# BLDC_conmutation_module.net
KiCad netlist of a schematic drawn in EAGLE
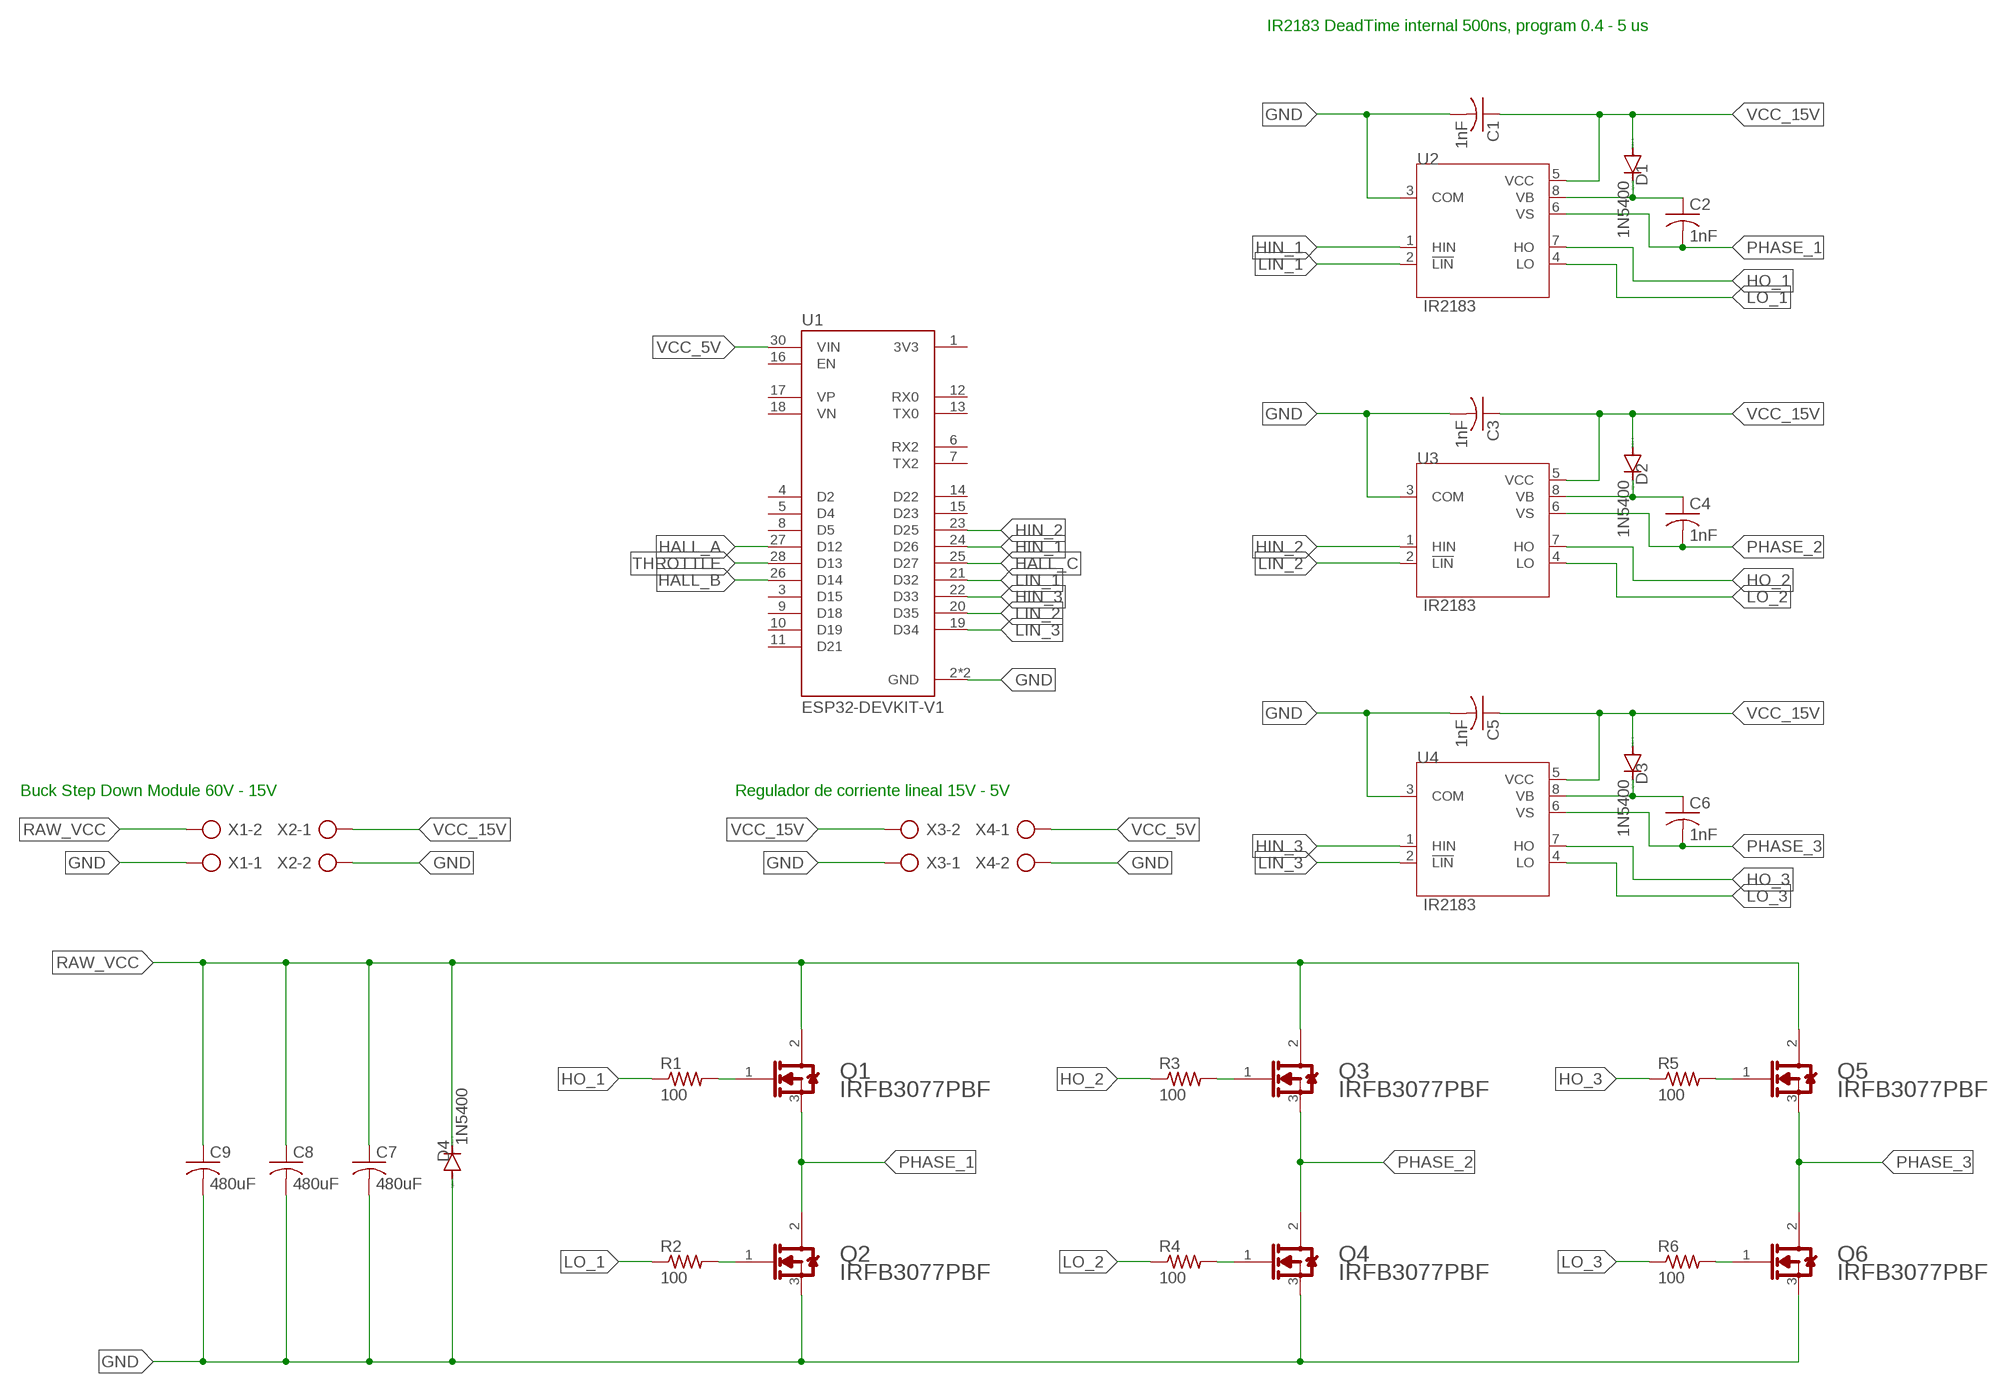
[diagram p0: schematic, sheet 1]

(export (version "E")
  (design (tool "Eeschema 10.0.6"))
  (components
    (comp (ref "C1")
      (value "1nF")
      (footprint "eagle-import:C025-050X050")
      (libsource (lib "eagle-import") (part "C-US025-050X050"))
    )
    (comp (ref "C2")
      (value "1nF")
      (footprint "eagle-import:C025-050X050")
      (libsource (lib "eagle-import") (part "C-US025-050X050"))
    )
    (comp (ref "C3")
      (value "1nF")
      (footprint "eagle-import:C025-050X050")
      (libsource (lib "eagle-import") (part "C-US025-050X050"))
    )
    (comp (ref "C4")
      (value "1nF")
      (footprint "eagle-import:C025-050X050")
      (libsource (lib "eagle-import") (part "C-US025-050X050"))
    )
    (comp (ref "C5")
      (value "1nF")
      (footprint "eagle-import:C025-050X050")
      (libsource (lib "eagle-import") (part "C-US025-050X050"))
    )
    (comp (ref "C6")
      (value "1nF")
      (footprint "eagle-import:C025-050X050")
      (libsource (lib "eagle-import") (part "C-US025-050X050"))
    )
    (comp (ref "C7")
      (value "480uF")
      (footprint "eagle-import:C025-050X050")
      (libsource (lib "eagle-import") (part "C-US025-050X050"))
    )
    (comp (ref "C8")
      (value "480uF")
      (footprint "eagle-import:C025-050X050")
      (libsource (lib "eagle-import") (part "C-US025-050X050"))
    )
    (comp (ref "C9")
      (value "480uF")
      (footprint "eagle-import:C025-050X050")
      (libsource (lib "eagle-import") (part "C-US025-050X050"))
    )
    (comp (ref "D1")
      (value "1N5400")
      (footprint "eagle-import:DO201-15")
      (libsource (lib "eagle-import") (part "1N5400"))
    )
    (comp (ref "D2")
      (value "1N5400")
      (footprint "eagle-import:DO201-15")
      (libsource (lib "eagle-import") (part "1N5400"))
    )
    (comp (ref "D3")
      (value "1N5400")
      (footprint "eagle-import:DO201-15")
      (libsource (lib "eagle-import") (part "1N5400"))
    )
    (comp (ref "D4")
      (value "1N5400")
      (footprint "eagle-import:DO201-15")
      (libsource (lib "eagle-import") (part "1N5400"))
    )
    (comp (ref "Q1")
      (value "INFINEON_IRFB3077PBFINFINEON_IRFB3077PBF_0_0")
      (footprint "eagle-import:INFINEON_IRFB3077PBF_0")
      (fields
        (field (name "DIGIKEY_PART_NUMBER") "IRFB3077PBF-ND")
        (field (name "MF") "Infineon")
        (field (name "MOUSER_PART_NUMBER") "942-IRFB3077PBF")
      )
      (libsource (lib "eagle-import") (part "INFINEON_IRFB3077PBFINFINEON_IRFB3077PBF_0_0"))
    )
    (comp (ref "Q2")
      (value "INFINEON_IRFB3077PBFINFINEON_IRFB3077PBF_0_0")
      (footprint "eagle-import:INFINEON_IRFB3077PBF_0")
      (fields
        (field (name "DIGIKEY_PART_NUMBER") "IRFB3077PBF-ND")
        (field (name "MF") "Infineon")
        (field (name "MOUSER_PART_NUMBER") "942-IRFB3077PBF")
      )
      (libsource (lib "eagle-import") (part "INFINEON_IRFB3077PBFINFINEON_IRFB3077PBF_0_0"))
    )
    (comp (ref "Q3")
      (value "INFINEON_IRFB3077PBFINFINEON_IRFB3077PBF_0_0")
      (footprint "eagle-import:INFINEON_IRFB3077PBF_0")
      (fields
        (field (name "DIGIKEY_PART_NUMBER") "IRFB3077PBF-ND")
        (field (name "MF") "Infineon")
        (field (name "MOUSER_PART_NUMBER") "942-IRFB3077PBF")
      )
      (libsource (lib "eagle-import") (part "INFINEON_IRFB3077PBFINFINEON_IRFB3077PBF_0_0"))
    )
    (comp (ref "Q4")
      (value "INFINEON_IRFB3077PBFINFINEON_IRFB3077PBF_0_0")
      (footprint "eagle-import:INFINEON_IRFB3077PBF_0")
      (fields
        (field (name "DIGIKEY_PART_NUMBER") "IRFB3077PBF-ND")
        (field (name "MF") "Infineon")
        (field (name "MOUSER_PART_NUMBER") "942-IRFB3077PBF")
      )
      (libsource (lib "eagle-import") (part "INFINEON_IRFB3077PBFINFINEON_IRFB3077PBF_0_0"))
    )
    (comp (ref "Q5")
      (value "INFINEON_IRFB3077PBFINFINEON_IRFB3077PBF_0_0")
      (footprint "eagle-import:INFINEON_IRFB3077PBF_0")
      (fields
        (field (name "DIGIKEY_PART_NUMBER") "IRFB3077PBF-ND")
        (field (name "MF") "Infineon")
        (field (name "MOUSER_PART_NUMBER") "942-IRFB3077PBF")
      )
      (libsource (lib "eagle-import") (part "INFINEON_IRFB3077PBFINFINEON_IRFB3077PBF_0_0"))
    )
    (comp (ref "Q6")
      (value "INFINEON_IRFB3077PBFINFINEON_IRFB3077PBF_0_0")
      (footprint "eagle-import:INFINEON_IRFB3077PBF_0")
      (fields
        (field (name "DIGIKEY_PART_NUMBER") "IRFB3077PBF-ND")
        (field (name "MF") "Infineon")
        (field (name "MOUSER_PART_NUMBER") "942-IRFB3077PBF")
      )
      (libsource (lib "eagle-import") (part "INFINEON_IRFB3077PBFINFINEON_IRFB3077PBF_0_0"))
    )
    (comp (ref "R1")
      (value "100")
      (footprint "eagle-import:0207_10")
      (libsource (lib "eagle-import") (part "R-US_0207/10"))
    )
    (comp (ref "R2")
      (value "100")
      (footprint "eagle-import:0207_10")
      (libsource (lib "eagle-import") (part "R-US_0207/10"))
    )
    (comp (ref "R3")
      (value "100")
      (footprint "eagle-import:0207_10")
      (libsource (lib "eagle-import") (part "R-US_0207/10"))
    )
    (comp (ref "R4")
      (value "100")
      (footprint "eagle-import:0207_10")
      (libsource (lib "eagle-import") (part "R-US_0207/10"))
    )
    (comp (ref "R5")
      (value "100")
      (footprint "eagle-import:0207_10")
      (libsource (lib "eagle-import") (part "R-US_0207/10"))
    )
    (comp (ref "R6")
      (value "100")
      (footprint "eagle-import:0207_10")
      (libsource (lib "eagle-import") (part "R-US_0207/10"))
    )
    (comp (ref "U1")
      (value "ESP32-DEVKIT-V1")
      (footprint "eagle-import:MODULE_ESP32_DEVKIT_V1")
      (fields (field (name "MF") "Do it"))
      (libsource (lib "eagle-import") (part "ESP32-DEVKIT-V1"))
    )
    (comp (ref "U2")
      (value "IR2183")
      (footprint "eagle-import:DIP762W45P254L1092H533Q8")
      (fields (field (name "MF") "Infineon"))
      (libsource (lib "eagle-import") (part "IR2183"))
    )
    (comp (ref "U3")
      (value "IR2183")
      (footprint "eagle-import:DIP762W45P254L1092H533Q8")
      (fields (field (name "MF") "Infineon"))
      (libsource (lib "eagle-import") (part "IR2183"))
    )
    (comp (ref "U4")
      (value "IR2183")
      (footprint "eagle-import:DIP762W45P254L1092H533Q8")
      (fields (field (name "MF") "Infineon"))
      (libsource (lib "eagle-import") (part "IR2183"))
    )
    (comp (ref "X1")
      (value "AK500/2-H")
      (footprint "eagle-import:AK500_2-H")
      (libsource (lib "eagle-import") (part "AK500/2-H"))
    )
    (comp (ref "X2")
      (value "AK500/2-H")
      (footprint "eagle-import:AK500_2-H")
      (libsource (lib "eagle-import") (part "AK500/2-H"))
    )
    (comp (ref "X3")
      (value "AK500/2-H")
      (footprint "eagle-import:AK500_2-H")
      (libsource (lib "eagle-import") (part "AK500/2-H"))
    )
    (comp (ref "X4")
      (value "AK500/2-H")
      (footprint "eagle-import:AK500_2-H")
      (libsource (lib "eagle-import") (part "AK500/2-H"))
    )
  )
  (nets
    (net (code "1") (name "GND") (class "Default")
      (node (ref "C1") (pin "2") (pinfunction "2_2") (pintype "passive"))
      (node (ref "C3") (pin "2") (pinfunction "2_2") (pintype "passive"))
      (node (ref "C5") (pin "2") (pinfunction "2_2") (pintype "passive"))
      (node (ref "C7") (pin "2") (pinfunction "2_2") (pintype "passive"))
      (node (ref "C8") (pin "2") (pinfunction "2_2") (pintype "passive"))
      (node (ref "C9") (pin "2") (pinfunction "2_2") (pintype "passive"))
      (node (ref "D4") (pin "A") (pinfunction "A_A") (pintype "passive"))
      (node (ref "Q2") (pin "3") (pinfunction "S_3") (pintype "output"))
      (node (ref "Q4") (pin "3") (pinfunction "S_3") (pintype "output"))
      (node (ref "Q6") (pin "3") (pinfunction "S_3") (pintype "output"))
      (node (ref "U1") (pin "2") (pinfunction "GND_2") (pintype "power_in"))
      (node (ref "U1") (pin "29") (pinfunction "GND_29") (pintype "power_in"))
      (node (ref "U2") (pin "3") (pinfunction "COM_3") (pintype "bidirectional"))
      (node (ref "U3") (pin "3") (pinfunction "COM_3") (pintype "bidirectional"))
      (node (ref "U4") (pin "3") (pinfunction "COM_3") (pintype "bidirectional"))
      (node (ref "X1") (pin "1") (pinfunction "KL_1") (pintype "passive"))
      (node (ref "X2") (pin "2") (pinfunction "KL_2") (pintype "passive"))
      (node (ref "X3") (pin "1") (pinfunction "KL_1") (pintype "passive"))
      (node (ref "X4") (pin "2") (pinfunction "KL_2") (pintype "passive"))
    )
    (net (code "2") (name "HALL_A") (class "Default")
      (node (ref "U1") (pin "27") (pinfunction "D12_27") (pintype "bidirectional"))
    )
    (net (code "3") (name "HALL_B") (class "Default")
      (node (ref "U1") (pin "26") (pinfunction "D14_26") (pintype "bidirectional"))
    )
    (net (code "4") (name "HALL_C") (class "Default")
      (node (ref "U1") (pin "25") (pinfunction "D27_25") (pintype "bidirectional"))
    )
    (net (code "5") (name "HIN_1") (class "Default")
      (node (ref "U1") (pin "24") (pinfunction "D26_24") (pintype "bidirectional"))
      (node (ref "U2") (pin "1") (pinfunction "HIN_1") (pintype "input"))
    )
    (net (code "6") (name "HIN_2") (class "Default")
      (node (ref "U1") (pin "23") (pinfunction "D25_23") (pintype "bidirectional"))
      (node (ref "U3") (pin "1") (pinfunction "HIN_1") (pintype "input"))
    )
    (net (code "7") (name "HIN_3") (class "Default")
      (node (ref "U1") (pin "22") (pinfunction "D33_22") (pintype "bidirectional"))
      (node (ref "U4") (pin "1") (pinfunction "HIN_1") (pintype "input"))
    )
    (net (code "8") (name "HO_1") (class "Default")
      (node (ref "R1") (pin "1") (pinfunction "1_1") (pintype "passive"))
      (node (ref "U2") (pin "7") (pinfunction "HO_7") (pintype "output"))
    )
    (net (code "9") (name "HO_2") (class "Default")
      (node (ref "R3") (pin "1") (pinfunction "1_1") (pintype "passive"))
      (node (ref "U3") (pin "7") (pinfunction "HO_7") (pintype "output"))
    )
    (net (code "10") (name "HO_3") (class "Default")
      (node (ref "R5") (pin "1") (pinfunction "1_1") (pintype "passive"))
      (node (ref "U4") (pin "7") (pinfunction "HO_7") (pintype "output"))
    )
    (net (code "11") (name "LIN_1") (class "Default")
      (node (ref "U1") (pin "21") (pinfunction "D32_21") (pintype "bidirectional"))
      (node (ref "U2") (pin "2") (pinfunction "~{LIN}_2") (pintype "input"))
    )
    (net (code "12") (name "LIN_2") (class "Default")
      (node (ref "U1") (pin "20") (pinfunction "D35_20") (pintype "bidirectional"))
      (node (ref "U3") (pin "2") (pinfunction "~{LIN}_2") (pintype "input"))
    )
    (net (code "13") (name "LIN_3") (class "Default")
      (node (ref "U1") (pin "19") (pinfunction "D34_19") (pintype "bidirectional"))
      (node (ref "U4") (pin "2") (pinfunction "~{LIN}_2") (pintype "input"))
    )
    (net (code "14") (name "LO_1") (class "Default")
      (node (ref "R2") (pin "1") (pinfunction "1_1") (pintype "passive"))
      (node (ref "U2") (pin "4") (pinfunction "LO_4") (pintype "output"))
    )
    (net (code "15") (name "LO_2") (class "Default")
      (node (ref "R4") (pin "1") (pinfunction "1_1") (pintype "passive"))
      (node (ref "U3") (pin "4") (pinfunction "LO_4") (pintype "output"))
    )
    (net (code "16") (name "LO_3") (class "Default")
      (node (ref "R6") (pin "1") (pinfunction "1_1") (pintype "passive"))
      (node (ref "U4") (pin "4") (pinfunction "LO_4") (pintype "output"))
    )
    (net (code "17") (name "Net-(Q1-G)") (class "Default")
      (node (ref "Q1") (pin "1") (pinfunction "G_1") (pintype "passive"))
      (node (ref "R1") (pin "2") (pinfunction "2_2") (pintype "passive"))
    )
    (net (code "18") (name "Net-(Q2-G)") (class "Default")
      (node (ref "Q2") (pin "1") (pinfunction "G_1") (pintype "passive"))
      (node (ref "R2") (pin "2") (pinfunction "2_2") (pintype "passive"))
    )
    (net (code "19") (name "Net-(Q3-G)") (class "Default")
      (node (ref "Q3") (pin "1") (pinfunction "G_1") (pintype "passive"))
      (node (ref "R3") (pin "2") (pinfunction "2_2") (pintype "passive"))
    )
    (net (code "20") (name "Net-(Q4-G)") (class "Default")
      (node (ref "Q4") (pin "1") (pinfunction "G_1") (pintype "passive"))
      (node (ref "R4") (pin "2") (pinfunction "2_2") (pintype "passive"))
    )
    (net (code "21") (name "Net-(Q5-G)") (class "Default")
      (node (ref "Q5") (pin "1") (pinfunction "G_1") (pintype "passive"))
      (node (ref "R5") (pin "2") (pinfunction "2_2") (pintype "passive"))
    )
    (net (code "22") (name "Net-(Q6-G)") (class "Default")
      (node (ref "Q6") (pin "1") (pinfunction "G_1") (pintype "passive"))
      (node (ref "R6") (pin "2") (pinfunction "2_2") (pintype "passive"))
    )
    (net (code "23") (name "Net-(U2-VB)") (class "Default")
      (node (ref "C2") (pin "1") (pinfunction "1_1") (pintype "passive"))
      (node (ref "D1") (pin "C") (pinfunction "C_C") (pintype "passive"))
      (node (ref "U2") (pin "8") (pinfunction "VB_8") (pintype "power_in"))
    )
    (net (code "24") (name "Net-(U3-VB)") (class "Default")
      (node (ref "C4") (pin "1") (pinfunction "1_1") (pintype "passive"))
      (node (ref "D2") (pin "C") (pinfunction "C_C") (pintype "passive"))
      (node (ref "U3") (pin "8") (pinfunction "VB_8") (pintype "power_in"))
    )
    (net (code "25") (name "Net-(U4-VB)") (class "Default")
      (node (ref "C6") (pin "1") (pinfunction "1_1") (pintype "passive"))
      (node (ref "D3") (pin "C") (pinfunction "C_C") (pintype "passive"))
      (node (ref "U4") (pin "8") (pinfunction "VB_8") (pintype "power_in"))
    )
    (net (code "26") (name "PHASE_1") (class "Default")
      (node (ref "C2") (pin "2") (pinfunction "2_2") (pintype "passive"))
      (node (ref "Q1") (pin "3") (pinfunction "S_3") (pintype "output"))
      (node (ref "Q2") (pin "2") (pinfunction "D_2") (pintype "passive"))
      (node (ref "U2") (pin "6") (pinfunction "VS_6") (pintype "power_in"))
    )
    (net (code "27") (name "PHASE_2") (class "Default")
      (node (ref "C4") (pin "2") (pinfunction "2_2") (pintype "passive"))
      (node (ref "Q3") (pin "3") (pinfunction "S_3") (pintype "output"))
      (node (ref "Q4") (pin "2") (pinfunction "D_2") (pintype "passive"))
      (node (ref "U3") (pin "6") (pinfunction "VS_6") (pintype "power_in"))
    )
    (net (code "28") (name "PHASE_3") (class "Default")
      (node (ref "C6") (pin "2") (pinfunction "2_2") (pintype "passive"))
      (node (ref "Q5") (pin "3") (pinfunction "S_3") (pintype "output"))
      (node (ref "Q6") (pin "2") (pinfunction "D_2") (pintype "passive"))
      (node (ref "U4") (pin "6") (pinfunction "VS_6") (pintype "power_in"))
    )
    (net (code "29") (name "RAW_VCC") (class "Default")
      (node (ref "C7") (pin "1") (pinfunction "1_1") (pintype "passive"))
      (node (ref "C8") (pin "1") (pinfunction "1_1") (pintype "passive"))
      (node (ref "C9") (pin "1") (pinfunction "1_1") (pintype "passive"))
      (node (ref "D4") (pin "C") (pinfunction "C_C") (pintype "passive"))
      (node (ref "Q1") (pin "2") (pinfunction "D_2") (pintype "passive"))
      (node (ref "Q3") (pin "2") (pinfunction "D_2") (pintype "passive"))
      (node (ref "Q5") (pin "2") (pinfunction "D_2") (pintype "passive"))
      (node (ref "X1") (pin "2") (pinfunction "KL_2") (pintype "passive"))
    )
    (net (code "30") (name "THROTTLE") (class "Default")
      (node (ref "U1") (pin "28") (pinfunction "D13_28") (pintype "bidirectional"))
    )
    (net (code "31") (name "VCC_5V") (class "Default")
      (node (ref "U1") (pin "30") (pinfunction "VIN_30") (pintype "input"))
      (node (ref "X4") (pin "1") (pinfunction "KL_1") (pintype "passive"))
    )
    (net (code "32") (name "VCC_15V") (class "Default")
      (node (ref "C1") (pin "1") (pinfunction "1_1") (pintype "passive"))
      (node (ref "C3") (pin "1") (pinfunction "1_1") (pintype "passive"))
      (node (ref "C5") (pin "1") (pinfunction "1_1") (pintype "passive"))
      (node (ref "D1") (pin "A") (pinfunction "A_A") (pintype "passive"))
      (node (ref "D2") (pin "A") (pinfunction "A_A") (pintype "passive"))
      (node (ref "D3") (pin "A") (pinfunction "A_A") (pintype "passive"))
      (node (ref "U2") (pin "5") (pinfunction "VCC_5") (pintype "power_in"))
      (node (ref "U3") (pin "5") (pinfunction "VCC_5") (pintype "power_in"))
      (node (ref "U4") (pin "5") (pinfunction "VCC_5") (pintype "power_in"))
      (node (ref "X2") (pin "1") (pinfunction "KL_1") (pintype "passive"))
      (node (ref "X3") (pin "2") (pinfunction "KL_2") (pintype "passive"))
    )
    (net (code "33") (name "unconnected-(U1-3V3-Pad1)") (class "Default")
      (node (ref "U1") (pin "1") (pinfunction "3V3_1") (pintype "output"))
    )
    (net (code "34") (name "unconnected-(U1-D2-Pad4)") (class "Default")
      (node (ref "U1") (pin "4") (pinfunction "D2_4") (pintype "bidirectional"))
    )
    (net (code "35") (name "unconnected-(U1-D4-Pad5)") (class "Default")
      (node (ref "U1") (pin "5") (pinfunction "D4_5") (pintype "bidirectional"))
    )
    (net (code "36") (name "unconnected-(U1-D5-Pad8)") (class "Default")
      (node (ref "U1") (pin "8") (pinfunction "D5_8") (pintype "bidirectional"))
    )
    (net (code "37") (name "unconnected-(U1-D15-Pad3)") (class "Default")
      (node (ref "U1") (pin "3") (pinfunction "D15_3") (pintype "bidirectional"))
    )
    (net (code "38") (name "unconnected-(U1-D18-Pad9)") (class "Default")
      (node (ref "U1") (pin "9") (pinfunction "D18_9") (pintype "bidirectional"))
    )
    (net (code "39") (name "unconnected-(U1-D19-Pad10)") (class "Default")
      (node (ref "U1") (pin "10") (pinfunction "D19_10") (pintype "bidirectional"))
    )
    (net (code "40") (name "unconnected-(U1-D21-Pad11)") (class "Default")
      (node (ref "U1") (pin "11") (pinfunction "D21_11") (pintype "bidirectional"))
    )
    (net (code "41") (name "unconnected-(U1-D22-Pad14)") (class "Default")
      (node (ref "U1") (pin "14") (pinfunction "D22_14") (pintype "bidirectional"))
    )
    (net (code "42") (name "unconnected-(U1-D23-Pad15)") (class "Default")
      (node (ref "U1") (pin "15") (pinfunction "D23_15") (pintype "bidirectional"))
    )
    (net (code "43") (name "unconnected-(U1-EN-Pad16)") (class "Default")
      (node (ref "U1") (pin "16") (pinfunction "EN_16") (pintype "input"))
    )
    (net (code "44") (name "unconnected-(U1-RX0-Pad12)") (class "Default")
      (node (ref "U1") (pin "12") (pinfunction "RX0_12") (pintype "input"))
    )
    (net (code "45") (name "unconnected-(U1-RX2-Pad6)") (class "Default")
      (node (ref "U1") (pin "6") (pinfunction "RX2_6") (pintype "input"))
    )
    (net (code "46") (name "unconnected-(U1-TX0-Pad13)") (class "Default")
      (node (ref "U1") (pin "13") (pinfunction "TX0_13") (pintype "output"))
    )
    (net (code "47") (name "unconnected-(U1-TX2-Pad7)") (class "Default")
      (node (ref "U1") (pin "7") (pinfunction "TX2_7") (pintype "output"))
    )
    (net (code "48") (name "unconnected-(U1-VN-Pad18)") (class "Default")
      (node (ref "U1") (pin "18") (pinfunction "VN_18") (pintype "bidirectional"))
    )
    (net (code "49") (name "unconnected-(U1-VP-Pad17)") (class "Default")
      (node (ref "U1") (pin "17") (pinfunction "VP_17") (pintype "bidirectional"))
    )
  )
)
